# ARE_adaptadora_STM32_64pin.net
KiCad netlist of a schematic drawn in EAGLE
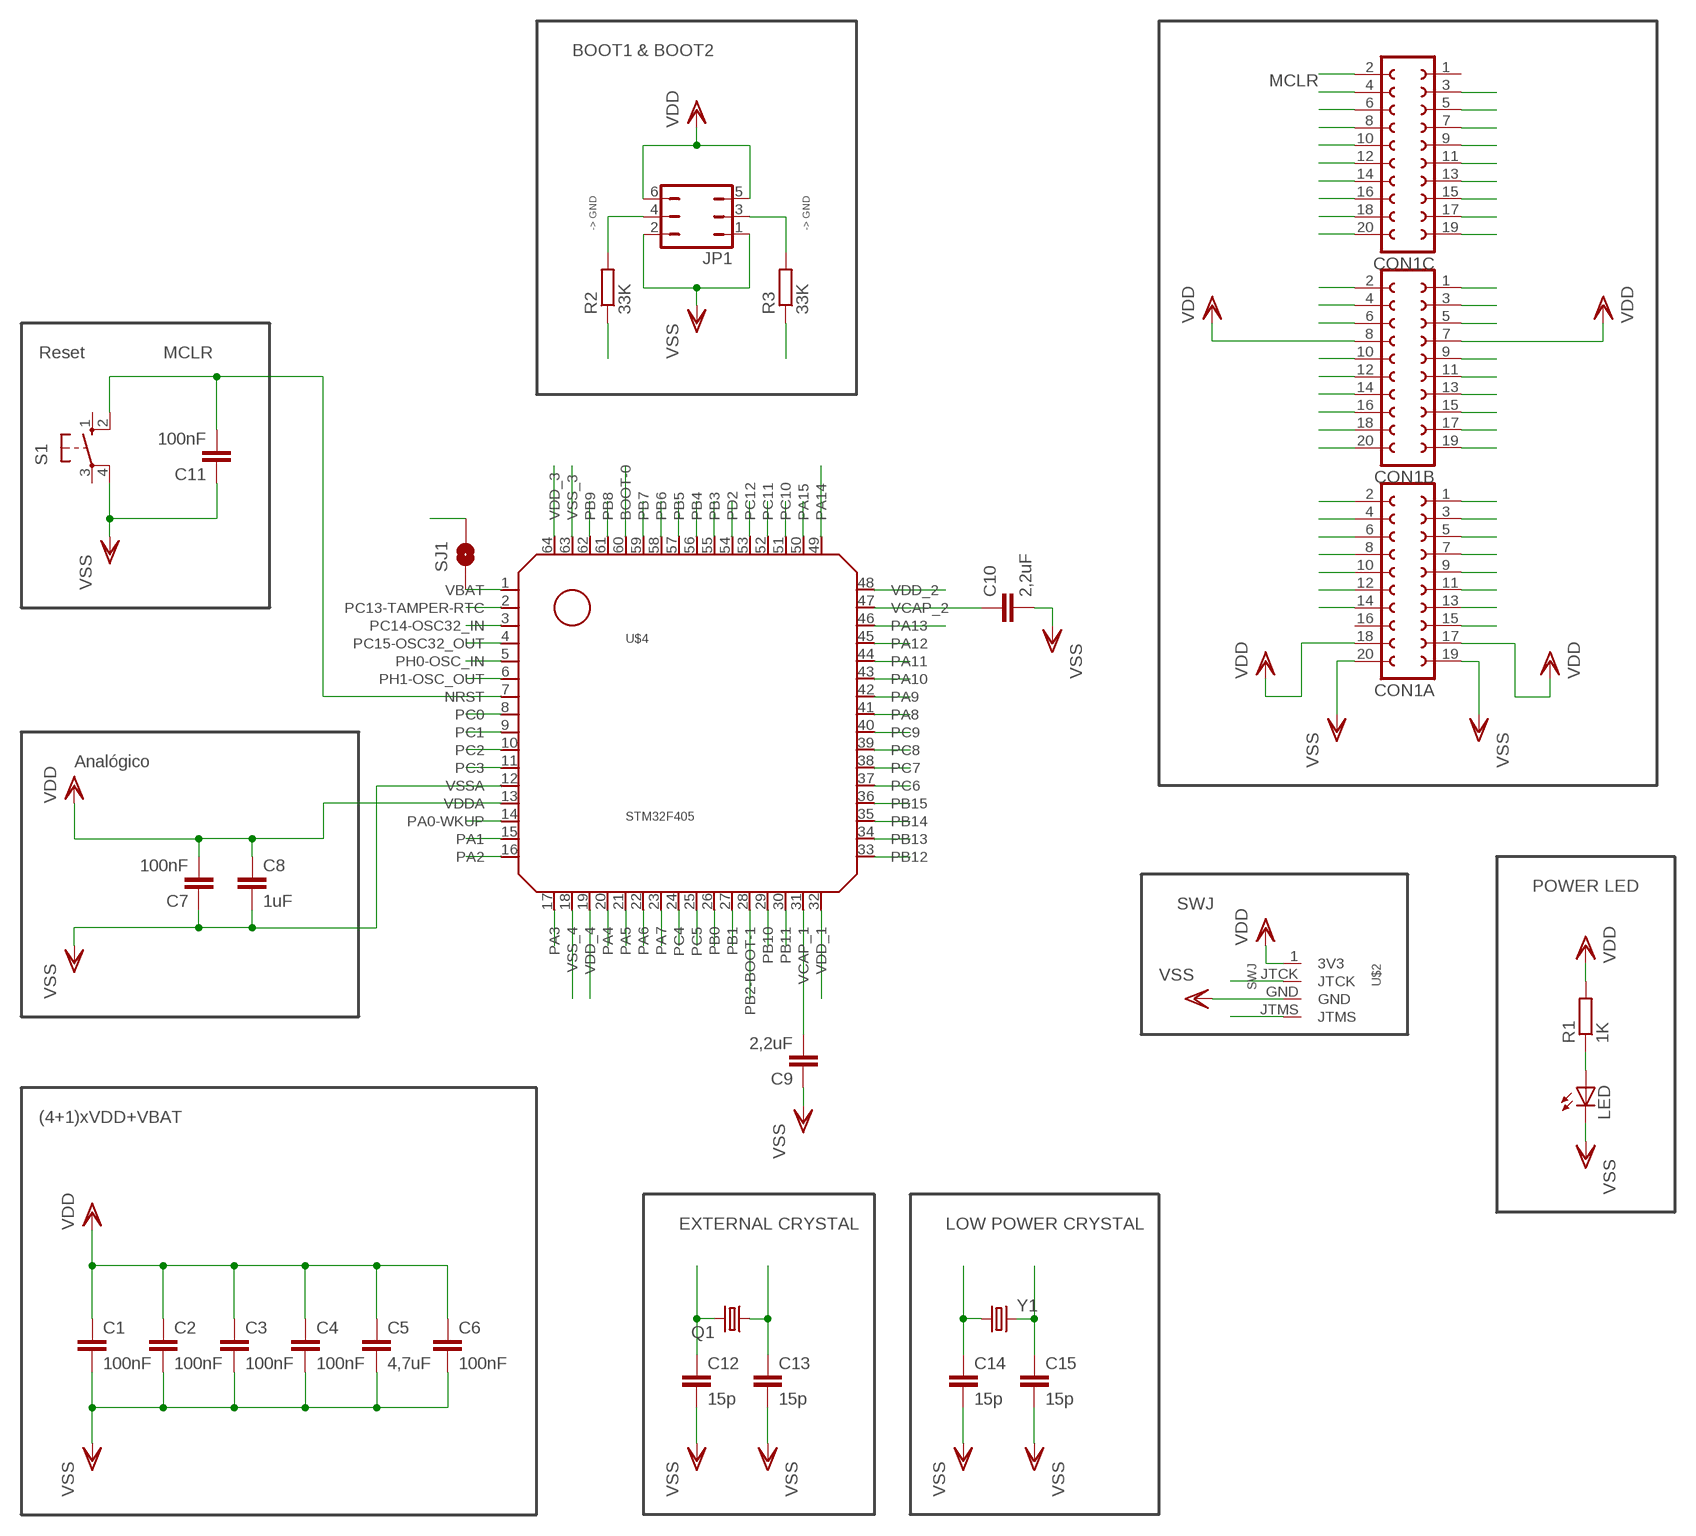
[diagram p0: schematic, sheet 1]

(export (version "E")
  (design (tool "Eeschema 10.0.6"))
  (components
    (comp (ref "C1")
      (value "100nF")
      (footprint "eagle-import:C0805K")
      (libsource (lib "eagle-import") (part "C-EUC0805K"))
    )
    (comp (ref "C2")
      (value "100nF")
      (footprint "eagle-import:C0805K")
      (libsource (lib "eagle-import") (part "C-EUC0805K"))
    )
    (comp (ref "C3")
      (value "100nF")
      (footprint "eagle-import:C0805K")
      (libsource (lib "eagle-import") (part "C-EUC0805K"))
    )
    (comp (ref "C4")
      (value "100nF")
      (footprint "eagle-import:C0805K")
      (libsource (lib "eagle-import") (part "C-EUC0805K"))
    )
    (comp (ref "C5")
      (value "4,7uF")
      (footprint "eagle-import:C0805K")
      (libsource (lib "eagle-import") (part "C-EUC0805K"))
    )
    (comp (ref "C6")
      (value "100nF")
      (footprint "eagle-import:C0805K")
      (libsource (lib "eagle-import") (part "C-EUC0805K"))
    )
    (comp (ref "C7")
      (value "100nF")
      (footprint "eagle-import:C0805K")
      (libsource (lib "eagle-import") (part "C-EUC0805K"))
    )
    (comp (ref "C8")
      (value "1uF")
      (footprint "eagle-import:C0805K")
      (libsource (lib "eagle-import") (part "C-EUC0805K"))
    )
    (comp (ref "C9")
      (value "2,2uF")
      (footprint "eagle-import:C0805K")
      (libsource (lib "eagle-import") (part "C-EUC0805K"))
    )
    (comp (ref "C10")
      (value "2,2uF")
      (footprint "eagle-import:C0805K")
      (libsource (lib "eagle-import") (part "C-EUC0805K"))
    )
    (comp (ref "C11")
      (value "100nF")
      (footprint "eagle-import:C0805K")
      (libsource (lib "eagle-import") (part "C-EUC0805K"))
    )
    (comp (ref "C12")
      (value "15p")
      (footprint "eagle-import:C0805")
      (libsource (lib "eagle-import") (part "C-EUC0805"))
    )
    (comp (ref "C13")
      (value "15p")
      (footprint "eagle-import:C0805")
      (libsource (lib "eagle-import") (part "C-EUC0805"))
    )
    (comp (ref "C14")
      (value "15p")
      (footprint "eagle-import:C0805")
      (libsource (lib "eagle-import") (part "C-EUC0805"))
    )
    (comp (ref "C15")
      (value "15p")
      (footprint "eagle-import:C0805")
      (libsource (lib "eagle-import") (part "C-EUC0805"))
    )
    (comp (ref "CON1A")
      (value "FE10-2W")
      (footprint "eagle-import:FE10-2W")
      (libsource (lib "eagle-import") (part "FE10-2W"))
    )
    (comp (ref "CON1B")
      (value "FE10-2W")
      (footprint "eagle-import:FE10-2W")
      (libsource (lib "eagle-import") (part "FE10-2W"))
    )
    (comp (ref "CON1C")
      (value "FE10-2W")
      (footprint "eagle-import:FE10-2W")
      (libsource (lib "eagle-import") (part "FE10-2W"))
    )
    (comp (ref "JP1")
      (value "JP3Q")
      (footprint "eagle-import:JP3Q")
      (libsource (lib "eagle-import") (part "JP3Q"))
    )
    (comp (ref "LED")
      (value "LEDCHIPLED_0805")
      (footprint "eagle-import:CHIPLED_0805")
      (libsource (lib "eagle-import") (part "LEDCHIPLED_0805"))
    )
    (comp (ref "Q1")
      (value "CRYSTALHC18U-V")
      (footprint "eagle-import:HC18U-V")
      (libsource (lib "eagle-import") (part "CRYSTALHC18U-V"))
    )
    (comp (ref "R1")
      (value "1K")
      (footprint "eagle-import:R0805")
      (libsource (lib "eagle-import") (part "R-EU_R0805"))
    )
    (comp (ref "R2")
      (value "33K")
      (footprint "eagle-import:R0805")
      (libsource (lib "eagle-import") (part "R-EU_R0805"))
    )
    (comp (ref "R3")
      (value "33K")
      (footprint "eagle-import:R0805")
      (libsource (lib "eagle-import") (part "R-EU_R0805"))
    )
    (comp (ref "S1")
      (value "10-XX")
      (footprint "eagle-import:B3F-10XX")
      (fields
        (field (name "MPN") "B3F-1000")
        (field (name "MPN_1") "B3F-1000")
        (field (name "OC_FARNELL") "176432")
        (field (name "OC_NEWARK") "36M3542")
      )
      (libsource (lib "eagle-import") (part "10-XX"))
    )
    (comp (ref "SJ1")
      (value "SOLDERJUMPERNO")
      (footprint "eagle-import:SJ_2S-NO")
      (libsource (lib "eagle-import") (part "SOLDERJUMPERNO"))
    )
    (comp (ref "U$2")
      (value "SWJ")
      (footprint "eagle-import:SWJ")
      (libsource (lib "eagle-import") (part "SWJ"))
    )
    (comp (ref "U$4")
      (value "STM32F405")
      (footprint "eagle-import:LQFP64")
      (libsource (lib "eagle-import") (part "STM32F405"))
    )
    (comp (ref "Y1")
      (value "CRYSTAL32-SMD")
      (footprint "eagle-import:CRYSTAL-32KHZ-SMD")
      (libsource (lib "eagle-import") (part "CRYSTAL32-SMD"))
    )
  )
  (nets
    (net (code "1") (name "/BOOT0") (class "Default")
      (node (ref "R2") (pin "1") (pinfunction "1_1") (pintype "passive"))
      (node (ref "U$4") (pin "60") (pinfunction "BOOT-0_60") (pintype "bidirectional"))
    )
    (net (code "2") (name "/BOOT1") (class "Default")
      (node (ref "CON1B") (pin "3") (pinfunction "3_3") (pintype "passive"))
      (node (ref "R3") (pin "1") (pinfunction "1_1") (pintype "passive"))
      (node (ref "U$4") (pin "28") (pinfunction "PB2-BOOT-1_28") (pintype "bidirectional"))
    )
    (net (code "3") (name "/JTCK") (class "Default")
      (node (ref "CON1A") (pin "3") (pinfunction "3_3") (pintype "passive"))
      (node (ref "U$2") (pin "JTCK") (pinfunction "JTCK_JTCK") (pintype "bidirectional"))
      (node (ref "U$4") (pin "49") (pinfunction "PA14_49") (pintype "bidirectional"))
    )
    (net (code "4") (name "/JTMS") (class "Default")
      (node (ref "CON1A") (pin "2") (pinfunction "2_2") (pintype "passive"))
      (node (ref "U$2") (pin "JTMS") (pinfunction "JTMS_JTMS") (pintype "bidirectional"))
      (node (ref "U$4") (pin "46") (pinfunction "PA13_46") (pintype "bidirectional"))
    )
    (net (code "5") (name "/MCLR") (class "Default")
      (node (ref "C11") (pin "2") (pinfunction "2_2") (pintype "passive"))
      (node (ref "CON1C") (pin "2") (pinfunction "2_2") (pintype "passive"))
      (node (ref "S1") (pin "2") (pinfunction "S1_2") (pintype "passive"))
      (node (ref "U$4") (pin "7") (pinfunction "NRST_7") (pintype "bidirectional"))
    )
    (net (code "6") (name "/N$24") (class "Default")
      (node (ref "CON1C") (pin "4") (pinfunction "4_4") (pintype "passive"))
      (node (ref "U$4") (pin "2") (pinfunction "PC13-TAMPER-RTC_2") (pintype "bidirectional"))
    )
    (net (code "7") (name "/N$33") (class "Default")
      (node (ref "CON1C") (pin "7") (pinfunction "7_7") (pintype "passive"))
      (node (ref "U$4") (pin "8") (pinfunction "PC0_8") (pintype "bidirectional"))
    )
    (net (code "8") (name "/N$34") (class "Default")
      (node (ref "CON1C") (pin "10") (pinfunction "10_10") (pintype "passive"))
      (node (ref "U$4") (pin "9") (pinfunction "PC1_9") (pintype "bidirectional"))
    )
    (net (code "9") (name "/N$35") (class "Default")
      (node (ref "CON1C") (pin "9") (pinfunction "9_9") (pintype "passive"))
      (node (ref "U$4") (pin "10") (pinfunction "PC2_10") (pintype "bidirectional"))
    )
    (net (code "10") (name "/N$36") (class "Default")
      (node (ref "CON1C") (pin "12") (pinfunction "12_12") (pintype "passive"))
      (node (ref "U$4") (pin "11") (pinfunction "PC3_11") (pintype "bidirectional"))
    )
    (net (code "11") (name "/N$37") (class "Default")
      (node (ref "CON1C") (pin "11") (pinfunction "11_11") (pintype "passive"))
      (node (ref "U$4") (pin "14") (pinfunction "PA0-WKUP_14") (pintype "bidirectional"))
    )
    (net (code "12") (name "/N$38") (class "Default")
      (node (ref "CON1C") (pin "14") (pinfunction "14_14") (pintype "passive"))
      (node (ref "U$4") (pin "15") (pinfunction "PA1_15") (pintype "bidirectional"))
    )
    (net (code "13") (name "/N$39") (class "Default")
      (node (ref "CON1C") (pin "13") (pinfunction "13_13") (pintype "passive"))
      (node (ref "U$4") (pin "16") (pinfunction "PA2_16") (pintype "bidirectional"))
    )
    (net (code "14") (name "/N$40") (class "Default")
      (node (ref "CON1C") (pin "16") (pinfunction "16_16") (pintype "passive"))
      (node (ref "U$4") (pin "17") (pinfunction "PA3_17") (pintype "bidirectional"))
    )
    (net (code "15") (name "/N$41") (class "Default")
      (node (ref "CON1C") (pin "15") (pinfunction "15_15") (pintype "passive"))
      (node (ref "U$4") (pin "20") (pinfunction "PA4_20") (pintype "bidirectional"))
    )
    (net (code "16") (name "/N$42") (class "Default")
      (node (ref "CON1C") (pin "18") (pinfunction "18_18") (pintype "passive"))
      (node (ref "U$4") (pin "21") (pinfunction "PA5_21") (pintype "bidirectional"))
    )
    (net (code "17") (name "/N$43") (class "Default")
      (node (ref "CON1C") (pin "17") (pinfunction "17_17") (pintype "passive"))
      (node (ref "U$4") (pin "22") (pinfunction "PA6_22") (pintype "bidirectional"))
    )
    (net (code "18") (name "/N$44") (class "Default")
      (node (ref "CON1C") (pin "20") (pinfunction "20_20") (pintype "passive"))
      (node (ref "U$4") (pin "23") (pinfunction "PA7_23") (pintype "bidirectional"))
    )
    (net (code "19") (name "/N$45") (class "Default")
      (node (ref "CON1C") (pin "19") (pinfunction "19_19") (pintype "passive"))
      (node (ref "U$4") (pin "24") (pinfunction "PC4_24") (pintype "bidirectional"))
    )
    (net (code "20") (name "/N$46") (class "Default")
      (node (ref "CON1B") (pin "2") (pinfunction "2_2") (pintype "passive"))
      (node (ref "U$4") (pin "25") (pinfunction "PC5_25") (pintype "bidirectional"))
    )
    (net (code "21") (name "/N$47") (class "Default")
      (node (ref "CON1B") (pin "1") (pinfunction "1_1") (pintype "passive"))
      (node (ref "U$4") (pin "26") (pinfunction "PB0_26") (pintype "bidirectional"))
    )
    (net (code "22") (name "/N$48") (class "Default")
      (node (ref "CON1B") (pin "4") (pinfunction "4_4") (pintype "passive"))
      (node (ref "U$4") (pin "27") (pinfunction "PB1_27") (pintype "bidirectional"))
    )
    (net (code "23") (name "/N$49") (class "Default")
      (node (ref "CON1B") (pin "6") (pinfunction "6_6") (pintype "passive"))
      (node (ref "U$4") (pin "29") (pinfunction "PB10_29") (pintype "bidirectional"))
    )
    (net (code "24") (name "/N$50") (class "Default")
      (node (ref "CON1B") (pin "5") (pinfunction "5_5") (pintype "passive"))
      (node (ref "U$4") (pin "30") (pinfunction "PB11_30") (pintype "bidirectional"))
    )
    (net (code "25") (name "/N$51") (class "Default")
      (node (ref "CON1B") (pin "9") (pinfunction "9_9") (pintype "passive"))
      (node (ref "U$4") (pin "33") (pinfunction "PB12_33") (pintype "bidirectional"))
    )
    (net (code "26") (name "/N$52") (class "Default")
      (node (ref "CON1B") (pin "10") (pinfunction "10_10") (pintype "passive"))
      (node (ref "U$4") (pin "34") (pinfunction "PB13_34") (pintype "bidirectional"))
    )
    (net (code "27") (name "/N$53") (class "Default")
      (node (ref "CON1B") (pin "11") (pinfunction "11_11") (pintype "passive"))
      (node (ref "U$4") (pin "35") (pinfunction "PB14_35") (pintype "bidirectional"))
    )
    (net (code "28") (name "/N$54") (class "Default")
      (node (ref "CON1B") (pin "12") (pinfunction "12_12") (pintype "passive"))
      (node (ref "U$4") (pin "36") (pinfunction "PB15_36") (pintype "bidirectional"))
    )
    (net (code "29") (name "/N$55") (class "Default")
      (node (ref "CON1B") (pin "13") (pinfunction "13_13") (pintype "passive"))
      (node (ref "U$4") (pin "37") (pinfunction "PC6_37") (pintype "bidirectional"))
    )
    (net (code "30") (name "/N$56") (class "Default")
      (node (ref "CON1B") (pin "14") (pinfunction "14_14") (pintype "passive"))
      (node (ref "U$4") (pin "38") (pinfunction "PC7_38") (pintype "bidirectional"))
    )
    (net (code "31") (name "/N$57") (class "Default")
      (node (ref "CON1B") (pin "15") (pinfunction "15_15") (pintype "passive"))
      (node (ref "U$4") (pin "39") (pinfunction "PC8_39") (pintype "bidirectional"))
    )
    (net (code "32") (name "/N$58") (class "Default")
      (node (ref "CON1B") (pin "16") (pinfunction "16_16") (pintype "passive"))
      (node (ref "U$4") (pin "40") (pinfunction "PC9_40") (pintype "bidirectional"))
    )
    (net (code "33") (name "/N$59") (class "Default")
      (node (ref "CON1B") (pin "17") (pinfunction "17_17") (pintype "passive"))
      (node (ref "U$4") (pin "41") (pinfunction "PA8_41") (pintype "bidirectional"))
    )
    (net (code "34") (name "/N$60") (class "Default")
      (node (ref "CON1B") (pin "18") (pinfunction "18_18") (pintype "passive"))
      (node (ref "U$4") (pin "42") (pinfunction "PA9_42") (pintype "bidirectional"))
    )
    (net (code "35") (name "/N$61") (class "Default")
      (node (ref "CON1B") (pin "19") (pinfunction "19_19") (pintype "passive"))
      (node (ref "U$4") (pin "43") (pinfunction "PA10_43") (pintype "bidirectional"))
    )
    (net (code "36") (name "/N$62") (class "Default")
      (node (ref "CON1B") (pin "20") (pinfunction "20_20") (pintype "passive"))
      (node (ref "U$4") (pin "44") (pinfunction "PA11_44") (pintype "bidirectional"))
    )
    (net (code "37") (name "/N$63") (class "Default")
      (node (ref "CON1A") (pin "1") (pinfunction "1_1") (pintype "passive"))
      (node (ref "U$4") (pin "45") (pinfunction "PA12_45") (pintype "bidirectional"))
    )
    (net (code "38") (name "/N$64") (class "Default")
      (node (ref "CON1A") (pin "4") (pinfunction "4_4") (pintype "passive"))
      (node (ref "U$4") (pin "50") (pinfunction "PA15_50") (pintype "bidirectional"))
    )
    (net (code "39") (name "/N$65") (class "Default")
      (node (ref "CON1A") (pin "5") (pinfunction "5_5") (pintype "passive"))
      (node (ref "U$4") (pin "51") (pinfunction "PC10_51") (pintype "bidirectional"))
    )
    (net (code "40") (name "/N$66") (class "Default")
      (node (ref "CON1A") (pin "6") (pinfunction "6_6") (pintype "passive"))
      (node (ref "U$4") (pin "52") (pinfunction "PC11_52") (pintype "bidirectional"))
    )
    (net (code "41") (name "/N$67") (class "Default")
      (node (ref "CON1A") (pin "7") (pinfunction "7_7") (pintype "passive"))
      (node (ref "U$4") (pin "53") (pinfunction "PC12_53") (pintype "bidirectional"))
    )
    (net (code "42") (name "/N$68") (class "Default")
      (node (ref "CON1A") (pin "8") (pinfunction "8_8") (pintype "passive"))
      (node (ref "U$4") (pin "54") (pinfunction "PD2_54") (pintype "bidirectional"))
    )
    (net (code "43") (name "/N$69") (class "Default")
      (node (ref "CON1A") (pin "9") (pinfunction "9_9") (pintype "passive"))
      (node (ref "U$4") (pin "55") (pinfunction "PB3_55") (pintype "bidirectional"))
    )
    (net (code "44") (name "/N$70") (class "Default")
      (node (ref "CON1A") (pin "10") (pinfunction "10_10") (pintype "passive"))
      (node (ref "U$4") (pin "56") (pinfunction "PB4_56") (pintype "bidirectional"))
    )
    (net (code "45") (name "/N$72") (class "Default")
      (node (ref "CON1A") (pin "11") (pinfunction "11_11") (pintype "passive"))
      (node (ref "U$4") (pin "57") (pinfunction "PB5_57") (pintype "bidirectional"))
    )
    (net (code "46") (name "/N$73") (class "Default")
      (node (ref "CON1A") (pin "12") (pinfunction "12_12") (pintype "passive"))
      (node (ref "U$4") (pin "58") (pinfunction "PB6_58") (pintype "bidirectional"))
    )
    (net (code "47") (name "/N$74") (class "Default")
      (node (ref "CON1A") (pin "13") (pinfunction "13_13") (pintype "passive"))
      (node (ref "U$4") (pin "59") (pinfunction "PB7_59") (pintype "bidirectional"))
    )
    (net (code "48") (name "/N$75") (class "Default")
      (node (ref "CON1A") (pin "14") (pinfunction "14_14") (pintype "passive"))
      (node (ref "U$4") (pin "61") (pinfunction "PB8_61") (pintype "bidirectional"))
    )
    (net (code "49") (name "/N$76") (class "Default")
      (node (ref "CON1A") (pin "15") (pinfunction "15_15") (pintype "passive"))
      (node (ref "U$4") (pin "62") (pinfunction "PB9_62") (pintype "bidirectional"))
    )
    (net (code "50") (name "/P12OSC0") (class "Default")
      (node (ref "C13") (pin "1") (pinfunction "1_1") (pintype "passive"))
      (node (ref "CON1C") (pin "5") (pinfunction "5_5") (pintype "passive"))
      (node (ref "Q1") (pin "1") (pinfunction "1_1") (pintype "passive"))
      (node (ref "U$4") (pin "5") (pinfunction "PH0-OSC_IN_5") (pintype "bidirectional"))
    )
    (net (code "51") (name "/P12OSC1") (class "Default")
      (node (ref "C12") (pin "1") (pinfunction "1_1") (pintype "passive"))
      (node (ref "CON1C") (pin "8") (pinfunction "8_8") (pintype "passive"))
      (node (ref "Q1") (pin "2") (pinfunction "2_2") (pintype "passive"))
      (node (ref "U$4") (pin "6") (pinfunction "PH1-OSC_OUT_6") (pintype "bidirectional"))
    )
    (net (code "52") (name "/P12OSC320") (class "Default")
      (node (ref "C14") (pin "1") (pinfunction "1_1") (pintype "passive"))
      (node (ref "CON1C") (pin "3") (pinfunction "3_3") (pintype "passive"))
      (node (ref "U$4") (pin "3") (pinfunction "PC14-OSC32_IN_3") (pintype "bidirectional"))
      (node (ref "Y1") (pin "X1") (pinfunction "1_X1") (pintype "passive"))
    )
    (net (code "53") (name "/P12OSC321") (class "Default")
      (node (ref "C15") (pin "1") (pinfunction "1_1") (pintype "passive"))
      (node (ref "CON1C") (pin "6") (pinfunction "6_6") (pintype "passive"))
      (node (ref "U$4") (pin "4") (pinfunction "PC15-OSC32_OUT_4") (pintype "bidirectional"))
      (node (ref "Y1") (pin "X2") (pinfunction "2_X2") (pintype "passive"))
    )
    (net (code "54") (name "Net-(JP1-Pad3)") (class "Default")
      (node (ref "JP1") (pin "3") (pinfunction "3_3") (pintype "passive"))
      (node (ref "R3") (pin "2") (pinfunction "2_2") (pintype "passive"))
    )
    (net (code "55") (name "Net-(JP1-Pad4)") (class "Default")
      (node (ref "JP1") (pin "4") (pinfunction "4_4") (pintype "passive"))
      (node (ref "R2") (pin "2") (pinfunction "2_2") (pintype "passive"))
    )
    (net (code "56") (name "Net-(LED-PadA)") (class "Default")
      (node (ref "LED") (pin "A") (pinfunction "A_A") (pintype "passive"))
      (node (ref "R1") (pin "1") (pinfunction "1_1") (pintype "passive"))
    )
    (net (code "57") (name "Net-(U$4-VBAT)") (class "Default")
      (node (ref "SJ1") (pin "1") (pinfunction "1_1") (pintype "passive"))
      (node (ref "U$4") (pin "1") (pinfunction "VBAT_1") (pintype "bidirectional"))
    )
    (net (code "58") (name "Net-(U$4-VCAP_1)") (class "Default")
      (node (ref "C9") (pin "2") (pinfunction "2_2") (pintype "passive"))
      (node (ref "U$4") (pin "31") (pinfunction "VCAP_1_31") (pintype "bidirectional"))
    )
    (net (code "59") (name "Net-(U$4-VCAP_2)") (class "Default")
      (node (ref "C10") (pin "1") (pinfunction "1_1") (pintype "passive"))
      (node (ref "U$4") (pin "47") (pinfunction "VCAP_2_47") (pintype "bidirectional"))
    )
    (net (code "60") (name "VDD") (class "Default")
      (node (ref "C1") (pin "1") (pinfunction "1_1") (pintype "passive"))
      (node (ref "C2") (pin "1") (pinfunction "1_1") (pintype "passive"))
      (node (ref "C3") (pin "1") (pinfunction "1_1") (pintype "passive"))
      (node (ref "C4") (pin "1") (pinfunction "1_1") (pintype "passive"))
      (node (ref "C5") (pin "1") (pinfunction "1_1") (pintype "passive"))
      (node (ref "C6") (pin "1") (pinfunction "1_1") (pintype "passive"))
      (node (ref "C7") (pin "2") (pinfunction "2_2") (pintype "passive"))
      (node (ref "C8") (pin "1") (pinfunction "1_1") (pintype "passive"))
      (node (ref "CON1A") (pin "17") (pinfunction "17_17") (pintype "passive"))
      (node (ref "CON1A") (pin "18") (pinfunction "18_18") (pintype "passive"))
      (node (ref "CON1B") (pin "7") (pinfunction "7_7") (pintype "passive"))
      (node (ref "CON1B") (pin "8") (pinfunction "8_8") (pintype "passive"))
      (node (ref "JP1") (pin "5") (pinfunction "5_5") (pintype "passive"))
      (node (ref "JP1") (pin "6") (pinfunction "6_6") (pintype "passive"))
      (node (ref "R1") (pin "2") (pinfunction "2_2") (pintype "passive"))
      (node (ref "SJ1") (pin "2") (pinfunction "2_2") (pintype "passive"))
      (node (ref "U$2") (pin "1") (pinfunction "3V3_1") (pintype "bidirectional"))
      (node (ref "U$4") (pin "13") (pinfunction "VDDA_13") (pintype "bidirectional"))
      (node (ref "U$4") (pin "19") (pinfunction "VDD_4_19") (pintype "bidirectional"))
      (node (ref "U$4") (pin "32") (pinfunction "VDD_1_32") (pintype "bidirectional"))
      (node (ref "U$4") (pin "48") (pinfunction "VDD_2_48") (pintype "bidirectional"))
      (node (ref "U$4") (pin "64") (pinfunction "VDD_3_64") (pintype "bidirectional"))
    )
    (net (code "61") (name "VSS") (class "Default")
      (node (ref "C1") (pin "2") (pinfunction "2_2") (pintype "passive"))
      (node (ref "C10") (pin "2") (pinfunction "2_2") (pintype "passive"))
      (node (ref "C11") (pin "1") (pinfunction "1_1") (pintype "passive"))
      (node (ref "C12") (pin "2") (pinfunction "2_2") (pintype "passive"))
      (node (ref "C13") (pin "2") (pinfunction "2_2") (pintype "passive"))
      (node (ref "C14") (pin "2") (pinfunction "2_2") (pintype "passive"))
      (node (ref "C15") (pin "2") (pinfunction "2_2") (pintype "passive"))
      (node (ref "C2") (pin "2") (pinfunction "2_2") (pintype "passive"))
      (node (ref "C3") (pin "2") (pinfunction "2_2") (pintype "passive"))
      (node (ref "C4") (pin "2") (pinfunction "2_2") (pintype "passive"))
      (node (ref "C5") (pin "2") (pinfunction "2_2") (pintype "passive"))
      (node (ref "C6") (pin "2") (pinfunction "2_2") (pintype "passive"))
      (node (ref "C7") (pin "1") (pinfunction "1_1") (pintype "passive"))
      (node (ref "C8") (pin "2") (pinfunction "2_2") (pintype "passive"))
      (node (ref "C9") (pin "1") (pinfunction "1_1") (pintype "passive"))
      (node (ref "CON1A") (pin "19") (pinfunction "19_19") (pintype "passive"))
      (node (ref "CON1A") (pin "20") (pinfunction "20_20") (pintype "passive"))
      (node (ref "JP1") (pin "1") (pinfunction "1_1") (pintype "passive"))
      (node (ref "JP1") (pin "2") (pinfunction "2_2") (pintype "passive"))
      (node (ref "LED") (pin "C") (pinfunction "C_C") (pintype "passive"))
      (node (ref "S1") (pin "4") (pinfunction "P1_4") (pintype "passive"))
      (node (ref "U$2") (pin "GND") (pinfunction "GND_GND") (pintype "bidirectional"))
      (node (ref "U$4") (pin "12") (pinfunction "VSSA_12") (pintype "bidirectional"))
      (node (ref "U$4") (pin "18") (pinfunction "VSS_4_18") (pintype "bidirectional"))
      (node (ref "U$4") (pin "63") (pinfunction "VSS_3_63") (pintype "bidirectional"))
    )
    (net (code "62") (name "unconnected-(CON1A-Pad16)") (class "Default")
      (node (ref "CON1A") (pin "16") (pinfunction "16_16") (pintype "passive"))
    )
    (net (code "63") (name "unconnected-(CON1C-Pad1)") (class "Default")
      (node (ref "CON1C") (pin "1") (pinfunction "1_1") (pintype "passive"))
    )
    (net (code "64") (name "unconnected-(S1-P-Pad3)") (class "Default")
      (node (ref "S1") (pin "3") (pinfunction "P_3") (pintype "passive"))
    )
    (net (code "65") (name "unconnected-(S1-S-Pad1)") (class "Default")
      (node (ref "S1") (pin "1") (pinfunction "S_1") (pintype "passive"))
    )
  )
)
